# OUTPUT.net
KiCad netlist of a schematic drawn in Altium Designer
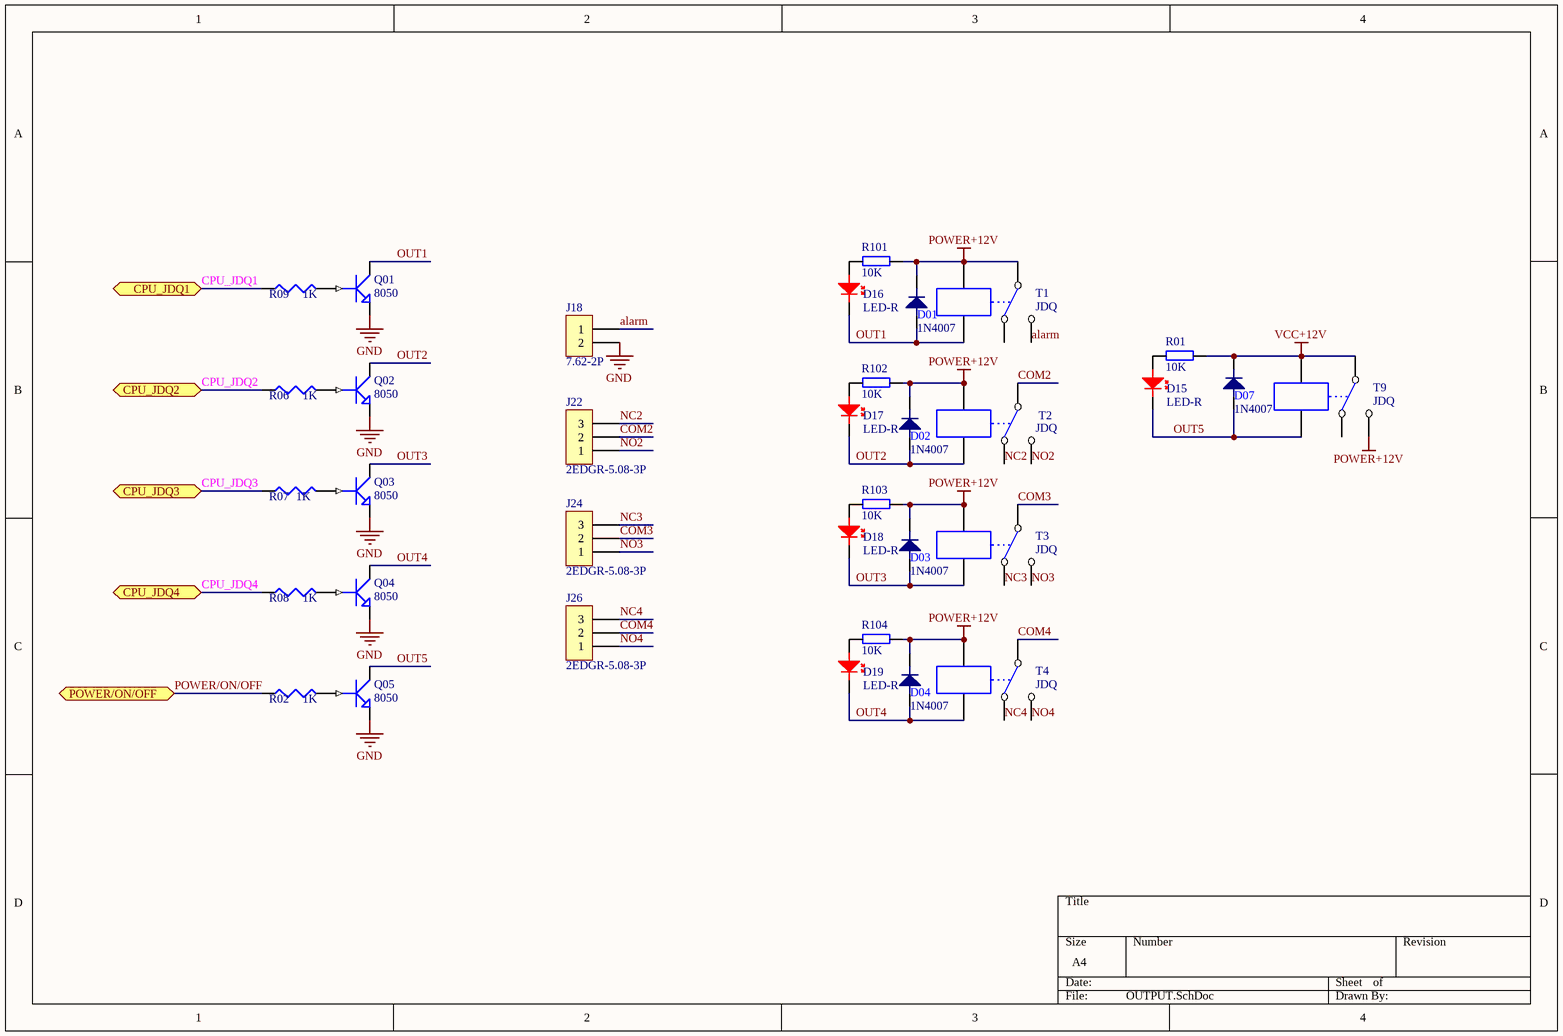
[diagram p0: OUTPUT.SchDoc]

(export (version "E")
  (design (tool "Eeschema 10.0.6"))
  (components
    (comp (ref "D01")
      (value "1N4007")
      (footprint "DO-214AC(SMA)")
      (description "1A整流二极管")
      (libsource (lib "mylib") (part "1N4007"))
    )
    (comp (ref "D02")
      (value "1N4007")
      (footprint "DO-214AC(SMA)")
      (description "1A整流二极管")
      (libsource (lib "mylib") (part "1N4007"))
    )
    (comp (ref "D03")
      (value "1N4007")
      (footprint "DO-214AC(SMA)")
      (description "1A整流二极管")
      (libsource (lib "mylib") (part "1N4007"))
    )
    (comp (ref "D04")
      (value "1N4007")
      (footprint "DO-214AC(SMA)")
      (description "1A整流二极管")
      (libsource (lib "mylib") (part "1N4007"))
    )
    (comp (ref "D07")
      (value "1N4007")
      (footprint "DO-214AC(SMA)")
      (description "1A整流二极管")
      (libsource (lib "mylib") (part "1N4007"))
    )
    (comp (ref "D15")
      (value "LED-R")
      (footprint "LED-0603")
      (description "红色LED")
      (libsource (lib "mylib") (part "LED-RED"))
    )
    (comp (ref "D16")
      (value "LED-R")
      (footprint "LED-0603")
      (description "绿色LED")
      (libsource (lib "mylib") (part "LED-RED"))
    )
    (comp (ref "D17")
      (value "LED-R")
      (footprint "LED-0603")
      (description "绿色LED")
      (libsource (lib "mylib") (part "LED-RED"))
    )
    (comp (ref "D18")
      (value "LED-R")
      (footprint "LED-0603")
      (description "绿色LED")
      (libsource (lib "mylib") (part "LED-RED"))
    )
    (comp (ref "D19")
      (value "LED-R")
      (footprint "LED-0603")
      (description "绿色LED")
      (libsource (lib "mylib") (part "LED-RED"))
    )
    (comp (ref "J18")
      (value "7.62-2P")
      (footprint "5.08-2P")
      (libsource (lib "INSPUR_SCH") (part "SIP2A-2.50（带槽）"))
    )
    (comp (ref "J22")
      (value "2EDGR-5.08-3P")
      (footprint "5.08-3P")
      (libsource (lib "INSPUR_PCB") (part "SIP3A-2.50（带槽）"))
    )
    (comp (ref "J24")
      (value "2EDGR-5.08-3P")
      (footprint "5.08-3P")
      (libsource (lib "INSPUR_PCB") (part "SIP3A-2.50（带槽）"))
    )
    (comp (ref "J26")
      (value "2EDGR-5.08-3P")
      (footprint "5.08-3P")
      (libsource (lib "INSPUR_PCB") (part "SIP3A-2.50（带槽）"))
    )
    (comp (ref "Q01") (value "8050") (footprint "SOT-23") (libsource (lib "INSPUR_SCH") (part "NPN1")))
    (comp (ref "Q02") (value "8050") (footprint "SOT-23") (libsource (lib "INSPUR_SCH") (part "NPN1")))
    (comp (ref "Q03") (value "8050") (footprint "SOT-23") (libsource (lib "INSPUR_SCH") (part "NPN1")))
    (comp (ref "Q04") (value "8050") (footprint "SOT-23") (libsource (lib "INSPUR_SCH") (part "NPN1")))
    (comp (ref "Q05") (value "8050") (footprint "SOT-23") (libsource (lib "INSPUR_SCH") (part "NPN1")))
    (comp (ref "R01") (value "10K") (footprint "0603") (libsource (lib "mylib") (part "Res")))
    (comp (ref "R02") (value "1K") (footprint "0603") (libsource (lib "INSPUR_SCH") (part "RES1")))
    (comp (ref "R06") (value "1K") (footprint "0603") (libsource (lib "INSPUR_SCH") (part "RES1")))
    (comp (ref "R07") (value "1K") (footprint "0603") (libsource (lib "INSPUR_SCH") (part "RES1")))
    (comp (ref "R08") (value "1K") (footprint "0603") (libsource (lib "INSPUR_SCH") (part "RES1")))
    (comp (ref "R09") (value "1K") (footprint "0603") (libsource (lib "INSPUR_SCH") (part "RES1")))
    (comp (ref "R101") (value "10K") (footprint "0603") (libsource (lib "mylib") (part "Res")))
    (comp (ref "R102") (value "10K") (footprint "0603") (libsource (lib "mylib") (part "Res")))
    (comp (ref "R103") (value "10K") (footprint "0603") (libsource (lib "mylib") (part "Res")))
    (comp (ref "R104") (value "10K") (footprint "0603") (libsource (lib "mylib") (part "Res")))
    (comp (ref "T1") (value "JDQ") (footprint "JDQ") (libsource (lib "INSPUR_SCH") (part "JDQ")))
    (comp (ref "T2") (value "JDQ") (footprint "JDQ") (libsource (lib "INSPUR_SCH") (part "JDQ")))
    (comp (ref "T3") (value "JDQ") (footprint "JDQ") (libsource (lib "INSPUR_SCH") (part "JDQ")))
    (comp (ref "T4") (value "JDQ") (footprint "JDQ") (libsource (lib "INSPUR_SCH") (part "JDQ")))
    (comp (ref "T9") (value "JDQ") (footprint "JDQ") (libsource (lib "INSPUR_SCH") (part "JDQ")))
  )
  (nets
    (net (code "1") (name "/COM2") (class "Default")
      (node (ref "J22") (pin "2") (pinfunction "2_2") (pintype "passive"))
      (node (ref "T2") (pin "1") (pinfunction "1_1") (pintype "passive"))
    )
    (net (code "2") (name "/COM3") (class "Default")
      (node (ref "J24") (pin "2") (pinfunction "2_2") (pintype "passive"))
      (node (ref "T3") (pin "1") (pinfunction "1_1") (pintype "passive"))
    )
    (net (code "3") (name "/COM4") (class "Default")
      (node (ref "J26") (pin "2") (pinfunction "2_2") (pintype "passive"))
      (node (ref "T4") (pin "1") (pinfunction "1_1") (pintype "passive"))
    )
    (net (code "4") (name "/CPU_JDQ1") (class "Default")
      (node (ref "R09") (pin "1") (pinfunction "1_1") (pintype "passive"))
    )
    (net (code "5") (name "/CPU_JDQ2") (class "Default")
      (node (ref "R06") (pin "1") (pinfunction "1_1") (pintype "passive"))
    )
    (net (code "6") (name "/CPU_JDQ3") (class "Default")
      (node (ref "R07") (pin "1") (pinfunction "1_1") (pintype "passive"))
    )
    (net (code "7") (name "/CPU_JDQ4") (class "Default")
      (node (ref "R08") (pin "1") (pinfunction "1_1") (pintype "passive"))
    )
    (net (code "8") (name "/NC2") (class "Default")
      (node (ref "J22") (pin "3") (pinfunction "3_3") (pintype "passive"))
      (node (ref "T2") (pin "3") (pinfunction "3_3") (pintype "passive"))
    )
    (net (code "9") (name "/NC3") (class "Default")
      (node (ref "J24") (pin "3") (pinfunction "3_3") (pintype "passive"))
      (node (ref "T3") (pin "3") (pinfunction "3_3") (pintype "passive"))
    )
    (net (code "10") (name "/NC4") (class "Default")
      (node (ref "J26") (pin "3") (pinfunction "3_3") (pintype "passive"))
      (node (ref "T4") (pin "3") (pinfunction "3_3") (pintype "passive"))
    )
    (net (code "11") (name "/NO2") (class "Default")
      (node (ref "J22") (pin "1") (pinfunction "1_1") (pintype "passive"))
      (node (ref "T2") (pin "2") (pinfunction "2_2") (pintype "passive"))
    )
    (net (code "12") (name "/NO3") (class "Default")
      (node (ref "J24") (pin "1") (pinfunction "1_1") (pintype "passive"))
      (node (ref "T3") (pin "2") (pinfunction "2_2") (pintype "passive"))
    )
    (net (code "13") (name "/NO4") (class "Default")
      (node (ref "J26") (pin "1") (pinfunction "1_1") (pintype "passive"))
      (node (ref "T4") (pin "2") (pinfunction "2_2") (pintype "passive"))
    )
    (net (code "14") (name "/OUT1") (class "Default")
      (node (ref "D01") (pin "1") (pintype "passive"))
      (node (ref "D16") (pin "2") (pintype "passive"))
      (node (ref "Q01") (pin "3") (pinfunction "C_3") (pintype "passive"))
      (node (ref "T1") (pin "5") (pinfunction "5_5") (pintype "passive"))
    )
    (net (code "15") (name "/OUT2") (class "Default")
      (node (ref "D02") (pin "1") (pintype "passive"))
      (node (ref "D17") (pin "2") (pintype "passive"))
      (node (ref "Q02") (pin "3") (pinfunction "C_3") (pintype "passive"))
      (node (ref "T2") (pin "5") (pinfunction "5_5") (pintype "passive"))
    )
    (net (code "16") (name "/OUT3") (class "Default")
      (node (ref "D03") (pin "1") (pintype "passive"))
      (node (ref "D18") (pin "2") (pintype "passive"))
      (node (ref "Q03") (pin "3") (pinfunction "C_3") (pintype "passive"))
      (node (ref "T3") (pin "5") (pinfunction "5_5") (pintype "passive"))
    )
    (net (code "17") (name "/OUT4") (class "Default")
      (node (ref "D04") (pin "1") (pintype "passive"))
      (node (ref "D19") (pin "2") (pintype "passive"))
      (node (ref "Q04") (pin "3") (pinfunction "C_3") (pintype "passive"))
      (node (ref "T4") (pin "5") (pinfunction "5_5") (pintype "passive"))
    )
    (net (code "18") (name "/OUT5") (class "Default")
      (node (ref "D07") (pin "1") (pintype "passive"))
      (node (ref "D15") (pin "2") (pintype "passive"))
      (node (ref "Q05") (pin "3") (pinfunction "C_3") (pintype "passive"))
      (node (ref "T9") (pin "5") (pinfunction "5_5") (pintype "passive"))
    )
    (net (code "19") (name "/POWER{slash}ON{slash}OFF") (class "Default")
      (node (ref "R02") (pin "1") (pinfunction "1_1") (pintype "passive"))
    )
    (net (code "20") (name "/alarm") (class "Default")
      (node (ref "J18") (pin "1") (pinfunction "1_1") (pintype "passive"))
      (node (ref "T1") (pin "2") (pinfunction "2_2") (pintype "passive"))
    )
    (net (code "21") (name "GND") (class "Default")
      (node (ref "J18") (pin "2") (pinfunction "2_2") (pintype "passive"))
      (node (ref "Q01") (pin "2") (pinfunction "E_2") (pintype "passive"))
      (node (ref "Q02") (pin "2") (pinfunction "E_2") (pintype "passive"))
      (node (ref "Q03") (pin "2") (pinfunction "E_2") (pintype "passive"))
      (node (ref "Q04") (pin "2") (pinfunction "E_2") (pintype "passive"))
      (node (ref "Q05") (pin "2") (pinfunction "E_2") (pintype "passive"))
    )
    (net (code "22") (name "Net-(D15-Pad1)") (class "Default")
      (node (ref "D15") (pin "1") (pintype "passive"))
      (node (ref "R01") (pin "2") (pintype "passive"))
    )
    (net (code "23") (name "Net-(D16-Pad1)") (class "Default")
      (node (ref "D16") (pin "1") (pintype "passive"))
      (node (ref "R101") (pin "2") (pintype "passive"))
    )
    (net (code "24") (name "Net-(D17-Pad1)") (class "Default")
      (node (ref "D17") (pin "1") (pintype "passive"))
      (node (ref "R102") (pin "2") (pintype "passive"))
    )
    (net (code "25") (name "Net-(D18-Pad1)") (class "Default")
      (node (ref "D18") (pin "1") (pintype "passive"))
      (node (ref "R103") (pin "2") (pintype "passive"))
    )
    (net (code "26") (name "Net-(D19-Pad1)") (class "Default")
      (node (ref "D19") (pin "1") (pintype "passive"))
      (node (ref "R104") (pin "2") (pintype "passive"))
    )
    (net (code "27") (name "Net-(Q01-B)") (class "Default")
      (node (ref "Q01") (pin "1") (pinfunction "B_1") (pintype "input"))
      (node (ref "R09") (pin "2") (pinfunction "2_2") (pintype "passive"))
    )
    (net (code "28") (name "Net-(Q02-B)") (class "Default")
      (node (ref "Q02") (pin "1") (pinfunction "B_1") (pintype "input"))
      (node (ref "R06") (pin "2") (pinfunction "2_2") (pintype "passive"))
    )
    (net (code "29") (name "Net-(Q03-B)") (class "Default")
      (node (ref "Q03") (pin "1") (pinfunction "B_1") (pintype "input"))
      (node (ref "R07") (pin "2") (pinfunction "2_2") (pintype "passive"))
    )
    (net (code "30") (name "Net-(Q04-B)") (class "Default")
      (node (ref "Q04") (pin "1") (pinfunction "B_1") (pintype "input"))
      (node (ref "R08") (pin "2") (pinfunction "2_2") (pintype "passive"))
    )
    (net (code "31") (name "Net-(Q05-B)") (class "Default")
      (node (ref "Q05") (pin "1") (pinfunction "B_1") (pintype "input"))
      (node (ref "R02") (pin "2") (pinfunction "2_2") (pintype "passive"))
    )
    (net (code "32") (name "POWER+12V") (class "Default")
      (node (ref "D01") (pin "2") (pintype "passive"))
      (node (ref "D02") (pin "2") (pintype "passive"))
      (node (ref "D03") (pin "2") (pintype "passive"))
      (node (ref "D04") (pin "2") (pintype "passive"))
      (node (ref "R101") (pin "1") (pintype "passive"))
      (node (ref "R102") (pin "1") (pintype "passive"))
      (node (ref "R103") (pin "1") (pintype "passive"))
      (node (ref "R104") (pin "1") (pintype "passive"))
      (node (ref "T1") (pin "1") (pinfunction "1_1") (pintype "passive"))
      (node (ref "T1") (pin "4") (pinfunction "4_4") (pintype "passive"))
      (node (ref "T2") (pin "4") (pinfunction "4_4") (pintype "passive"))
      (node (ref "T3") (pin "4") (pinfunction "4_4") (pintype "passive"))
      (node (ref "T4") (pin "4") (pinfunction "4_4") (pintype "passive"))
      (node (ref "T9") (pin "2") (pinfunction "2_2") (pintype "passive"))
    )
    (net (code "33") (name "VCC+12V") (class "Default")
      (node (ref "D07") (pin "2") (pintype "passive"))
      (node (ref "R01") (pin "1") (pintype "passive"))
      (node (ref "T9") (pin "1") (pinfunction "1_1") (pintype "passive"))
      (node (ref "T9") (pin "4") (pinfunction "4_4") (pintype "passive"))
    )
    (net (code "34") (name "unconnected-(T1-Pad3)") (class "Default")
      (node (ref "T1") (pin "3") (pinfunction "3_3") (pintype "passive"))
    )
    (net (code "35") (name "unconnected-(T9-Pad3)") (class "Default")
      (node (ref "T9") (pin "3") (pinfunction "3_3") (pintype "passive"))
    )
  )
)
